# sonar_DAQ.net
KiCad netlist of a schematic drawn in Altium Designer
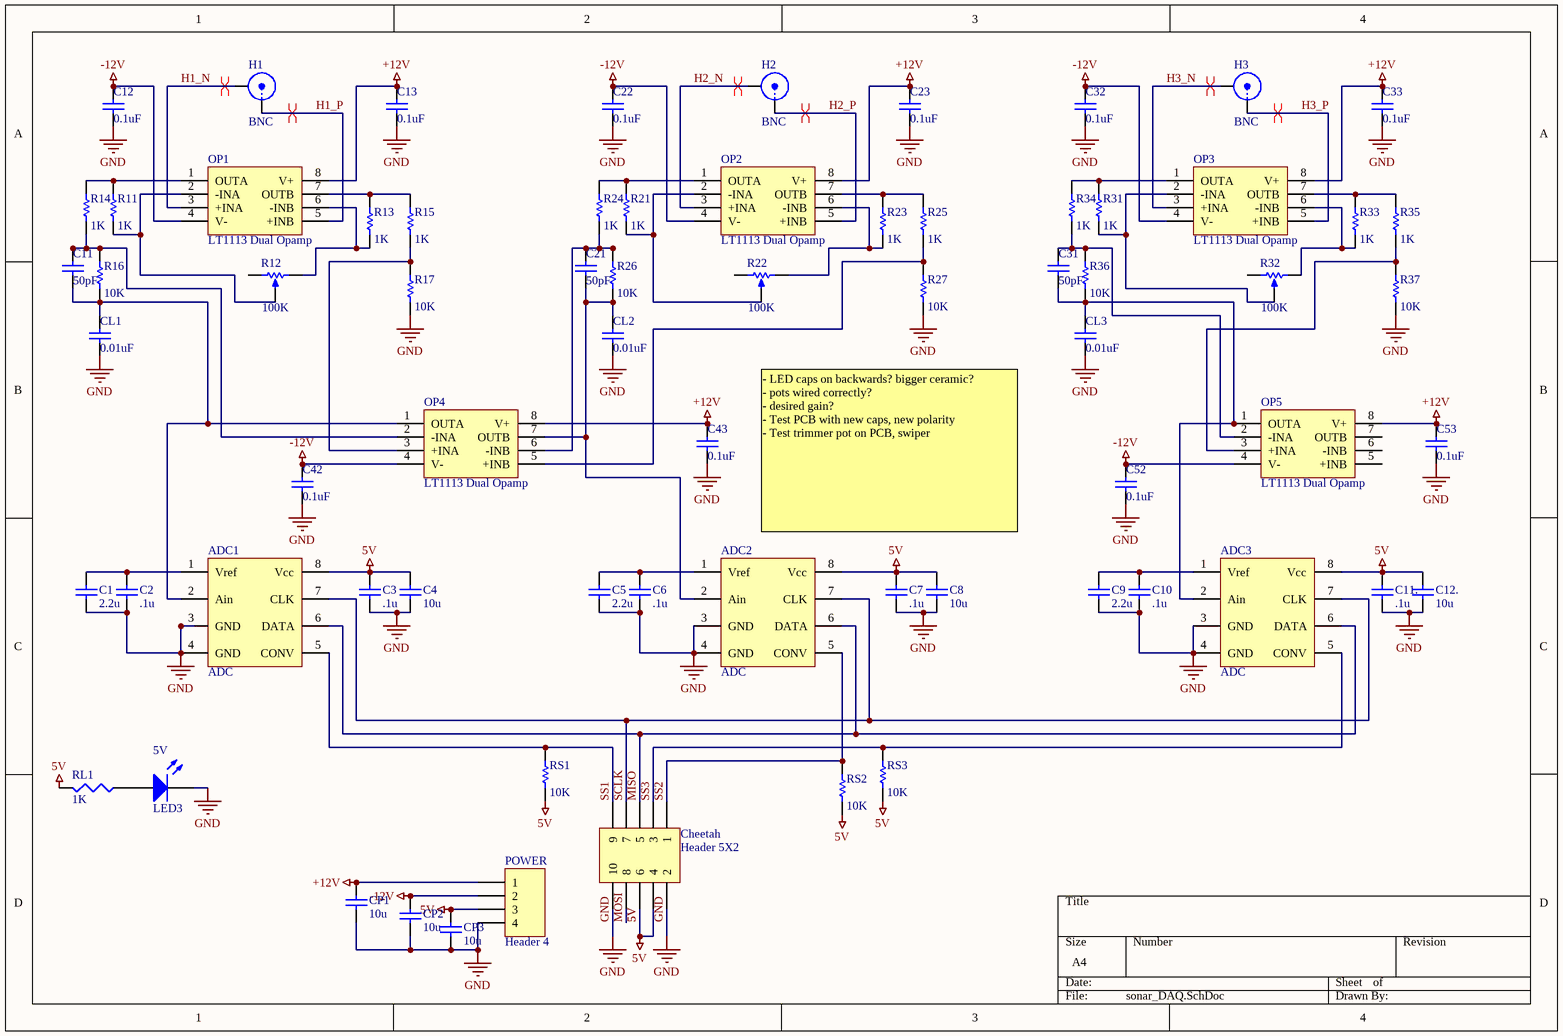
[diagram p0: sonar_DAQ.SchDoc]

(export (version "E")
  (design (tool "Eeschema 10.0.6"))
  (components
    (comp (ref "5V")
      (value "LED3")
      (footprint "0805_led")
      (description "Typical BLUE SiC LED")
      (fields (field (name "PUBLISHER") "Altium Limited"))
      (libsource (lib "Miscellaneous Devices") (part "LED3"))
    )
    (comp (ref "ADC1")
      (value "ADC")
      (footprint "ADC")
      (description "ADS7835")
      (libsource (lib "sonar_DAQ") (part "ADC"))
    )
    (comp (ref "ADC2")
      (value "ADC")
      (footprint "ADC")
      (description "ADS7835")
      (libsource (lib "sonar_DAQ") (part "ADC"))
    )
    (comp (ref "ADC3")
      (value "ADC")
      (footprint "ADC")
      (description "ADS7835")
      (libsource (lib "sonar_DAQ") (part "ADC"))
    )
    (comp (ref "C1")
      (value "2.2u")
      (footprint "0805_tantalum_cap")
      (description "Capacitor")
      (fields (field (name "PUBLISHER") "Altium Limited"))
      (libsource (lib "Miscellaneous Devices") (part "Cap"))
    )
    (comp (ref "C2")
      (value ".1u")
      (footprint "0805_ceramic_cap")
      (description "Capacitor")
      (fields (field (name "PUBLISHER") "Altium Limited"))
      (libsource (lib "Miscellaneous Devices") (part "Cap"))
    )
    (comp (ref "C3")
      (value ".1u")
      (footprint "0805_ceramic_cap")
      (description "Capacitor")
      (fields (field (name "PUBLISHER") "Altium Limited"))
      (libsource (lib "Miscellaneous Devices") (part "Cap"))
    )
    (comp (ref "C4")
      (value "10u")
      (footprint "0805_tantalum_cap")
      (description "Capacitor")
      (fields (field (name "PUBLISHER") "Altium Limited"))
      (libsource (lib "Miscellaneous Devices") (part "Cap"))
    )
    (comp (ref "C5")
      (value "2.2u")
      (footprint "0805_tantalum_cap")
      (description "Capacitor")
      (fields (field (name "PUBLISHER") "Altium Limited"))
      (libsource (lib "Miscellaneous Devices") (part "Cap"))
    )
    (comp (ref "C6")
      (value ".1u")
      (footprint "0805_ceramic_cap")
      (description "Capacitor")
      (fields (field (name "PUBLISHER") "Altium Limited"))
      (libsource (lib "Miscellaneous Devices") (part "Cap"))
    )
    (comp (ref "C7")
      (value ".1u")
      (footprint "0805_ceramic_cap")
      (description "Capacitor")
      (fields (field (name "PUBLISHER") "Altium Limited"))
      (libsource (lib "Miscellaneous Devices") (part "Cap"))
    )
    (comp (ref "C8")
      (value "10u")
      (footprint "0805_tantalum_cap")
      (description "Capacitor")
      (fields (field (name "PUBLISHER") "Altium Limited"))
      (libsource (lib "Miscellaneous Devices") (part "Cap"))
    )
    (comp (ref "C9")
      (value "2.2u")
      (footprint "0805_tantalum_cap")
      (description "Capacitor")
      (fields (field (name "PUBLISHER") "Altium Limited"))
      (libsource (lib "Miscellaneous Devices") (part "Cap"))
    )
    (comp (ref "C10")
      (value ".1u")
      (footprint "0805_ceramic_cap")
      (description "Capacitor")
      (fields (field (name "PUBLISHER") "Altium Limited"))
      (libsource (lib "Miscellaneous Devices") (part "Cap"))
    )
    (comp (ref "C11")
      (value "50pF")
      (footprint "0805_ceramic_cap")
      (description "Capacitor")
      (fields (field (name "Comment") "Cap") (field (name "PUBLISHER") "Altium Limited"))
      (libsource (lib "Miscellaneous Devices") (part "Cap"))
    )
    (comp (ref "C11.")
      (value ".1u")
      (footprint "0805_ceramic_cap")
      (description "Capacitor")
      (fields (field (name "PUBLISHER") "Altium Limited"))
      (libsource (lib "Miscellaneous Devices") (part "Cap"))
    )
    (comp (ref "C12")
      (value "0.1uF")
      (footprint "0805_ceramic_cap")
      (description "Capacitor")
      (fields (field (name "Comment") "Cap") (field (name "PUBLISHER") "Altium Limited"))
      (libsource (lib "Miscellaneous Devices") (part "Cap"))
    )
    (comp (ref "C12.")
      (value "10u")
      (footprint "0805_tantalum_cap")
      (description "Capacitor")
      (fields (field (name "PUBLISHER") "Altium Limited"))
      (libsource (lib "Miscellaneous Devices") (part "Cap"))
    )
    (comp (ref "C13")
      (value "0.1uF")
      (footprint "0805_ceramic_cap")
      (description "Capacitor")
      (fields (field (name "Comment") "Cap") (field (name "PUBLISHER") "Altium Limited"))
      (libsource (lib "Miscellaneous Devices") (part "Cap"))
    )
    (comp (ref "C21")
      (value "50pF")
      (footprint "0805_ceramic_cap")
      (description "Capacitor")
      (fields (field (name "Comment") "Cap") (field (name "PUBLISHER") "Altium Limited"))
      (libsource (lib "Miscellaneous Devices") (part "Cap"))
    )
    (comp (ref "C22")
      (value "0.1uF")
      (footprint "0805_ceramic_cap")
      (description "Capacitor")
      (fields (field (name "Comment") "Cap") (field (name "PUBLISHER") "Altium Limited"))
      (libsource (lib "Miscellaneous Devices") (part "Cap"))
    )
    (comp (ref "C23")
      (value "0.1uF")
      (footprint "0805_ceramic_cap")
      (description "Capacitor")
      (fields (field (name "Comment") "Cap") (field (name "PUBLISHER") "Altium Limited"))
      (libsource (lib "Miscellaneous Devices") (part "Cap"))
    )
    (comp (ref "C31")
      (value "50pF")
      (footprint "0805_ceramic_cap")
      (description "Capacitor")
      (fields (field (name "Comment") "Cap") (field (name "PUBLISHER") "Altium Limited"))
      (libsource (lib "Miscellaneous Devices") (part "Cap"))
    )
    (comp (ref "C32")
      (value "0.1uF")
      (footprint "0805_ceramic_cap")
      (description "Capacitor")
      (fields (field (name "Comment") "Cap") (field (name "PUBLISHER") "Altium Limited"))
      (libsource (lib "Miscellaneous Devices") (part "Cap"))
    )
    (comp (ref "C33")
      (value "0.1uF")
      (footprint "0805_ceramic_cap")
      (description "Capacitor")
      (fields (field (name "Comment") "Cap") (field (name "PUBLISHER") "Altium Limited"))
      (libsource (lib "Miscellaneous Devices") (part "Cap"))
    )
    (comp (ref "C42")
      (value "0.1uF")
      (footprint "0805_ceramic_cap")
      (description "Capacitor")
      (fields (field (name "Comment") "Cap") (field (name "PUBLISHER") "Altium Limited"))
      (libsource (lib "Miscellaneous Devices") (part "Cap"))
    )
    (comp (ref "C43")
      (value "0.1uF")
      (footprint "0805_ceramic_cap")
      (description "Capacitor")
      (fields (field (name "Comment") "Cap") (field (name "PUBLISHER") "Altium Limited"))
      (libsource (lib "Miscellaneous Devices") (part "Cap"))
    )
    (comp (ref "C52")
      (value "0.1uF")
      (footprint "0805_ceramic_cap")
      (description "Capacitor")
      (fields (field (name "Comment") "Cap") (field (name "PUBLISHER") "Altium Limited"))
      (libsource (lib "Miscellaneous Devices") (part "Cap"))
    )
    (comp (ref "C53")
      (value "0.1uF")
      (footprint "0805_ceramic_cap")
      (description "Capacitor")
      (fields (field (name "Comment") "Cap") (field (name "PUBLISHER") "Altium Limited"))
      (libsource (lib "Miscellaneous Devices") (part "Cap"))
    )
    (comp (ref "Cheetah")
      (value "Header 5X2")
      (footprint "HDR2X5")
      (description "Header, 5-Pin, Dual row")
      (fields (field (name "PUBLISHER") "Altium Limited"))
      (libsource (lib "Miscellaneous Connectors") (part "Header 5X2"))
    )
    (comp (ref "CL1")
      (value "0.01uF")
      (footprint "0805_ceramic_cap")
      (description "Capacitor")
      (fields (field (name "Comment") "Cap") (field (name "PUBLISHER") "Altium Limited"))
      (libsource (lib "Miscellaneous Devices") (part "Cap"))
    )
    (comp (ref "CL2")
      (value "0.01uF")
      (footprint "0805_ceramic_cap")
      (description "Capacitor")
      (fields (field (name "Comment") "Cap") (field (name "PUBLISHER") "Altium Limited"))
      (libsource (lib "Miscellaneous Devices") (part "Cap"))
    )
    (comp (ref "CL3")
      (value "0.01uF")
      (footprint "0805_ceramic_cap")
      (description "Capacitor")
      (fields (field (name "Comment") "Cap") (field (name "PUBLISHER") "Altium Limited"))
      (libsource (lib "Miscellaneous Devices") (part "Cap"))
    )
    (comp (ref "CP1")
      (value "10u")
      (footprint "1210_cap")
      (description "Capacitor")
      (fields (field (name "PUBLISHER") "Altium Limited"))
      (libsource (lib "Miscellaneous Devices") (part "Cap"))
    )
    (comp (ref "CP2")
      (value "10u")
      (footprint "1210_cap")
      (description "Capacitor")
      (fields (field (name "PUBLISHER") "Altium Limited"))
      (libsource (lib "Miscellaneous Devices") (part "Cap"))
    )
    (comp (ref "CP3")
      (value "10u")
      (footprint "1210_cap")
      (description "Capacitor")
      (fields (field (name "PUBLISHER") "Altium Limited"))
      (libsource (lib "Miscellaneous Devices") (part "Cap"))
    )
    (comp (ref "H1")
      (value "BNC")
      (footprint "BNC")
      (description "BNC Elbow Connector")
      (fields (field (name "PUBLISHER") "Altium Limited"))
      (libsource (lib "Miscellaneous Connectors") (part "BNC"))
    )
    (comp (ref "H2")
      (value "BNC")
      (footprint "BNC")
      (description "BNC Elbow Connector")
      (fields (field (name "PUBLISHER") "Altium Limited"))
      (libsource (lib "Miscellaneous Connectors") (part "BNC"))
    )
    (comp (ref "H3")
      (value "BNC")
      (footprint "BNC")
      (description "BNC Elbow Connector")
      (fields (field (name "PUBLISHER") "Altium Limited"))
      (libsource (lib "Miscellaneous Connectors") (part "BNC"))
    )
    (comp (ref "OP1")
      (value "LT1113 Dual Opamp")
      (footprint "lt1113_opamp")
      (libsource (lib "sonar_DAQ") (part "LT1113 OPAMP"))
    )
    (comp (ref "OP2")
      (value "LT1113 Dual Opamp")
      (footprint "lt1113_opamp")
      (libsource (lib "sonar_DAQ") (part "LT1113 OPAMP"))
    )
    (comp (ref "OP3")
      (value "LT1113 Dual Opamp")
      (footprint "lt1113_opamp")
      (libsource (lib "sonar_DAQ") (part "LT1113 OPAMP"))
    )
    (comp (ref "OP4")
      (value "LT1113 Dual Opamp")
      (footprint "lt1113_opamp")
      (libsource (lib "sonar_DAQ") (part "LT1113 OPAMP"))
    )
    (comp (ref "OP5")
      (value "LT1113 Dual Opamp")
      (footprint "lt1113_opamp")
      (libsource (lib "sonar_DAQ") (part "LT1113 OPAMP"))
    )
    (comp (ref "POWER")
      (value "Header 4")
      (footprint "HDR1X4")
      (description "Header, 4-Pin")
      (fields (field (name "PUBLISHER") "Altium Limited"))
      (libsource (lib "Miscellaneous Connectors") (part "Header 4"))
    )
    (comp (ref "R11")
      (value "1K")
      (footprint "0805_res")
      (description "Resistor")
      (fields (field (name "Comment") "Res1") (field (name "PUBLISHER") "Altium Limited"))
      (libsource (lib "Miscellaneous Devices") (part "Res1"))
    )
    (comp (ref "R12")
      (value "100K")
      (footprint "trimmer_pot")
      (description "Potentiometer")
      (fields (field (name "Comment") "RPot") (field (name "PUBLISHER") "Altium Limited"))
      (libsource (lib "Miscellaneous Devices") (part "RPot"))
    )
    (comp (ref "R13")
      (value "1K")
      (footprint "0805_res")
      (description "Resistor")
      (fields (field (name "Comment") "Res1") (field (name "PUBLISHER") "Altium Limited"))
      (libsource (lib "Miscellaneous Devices") (part "Res1"))
    )
    (comp (ref "R14")
      (value "1K")
      (footprint "0805_res")
      (description "Resistor")
      (fields (field (name "Comment") "Res1") (field (name "PUBLISHER") "Altium Limited"))
      (libsource (lib "Miscellaneous Devices") (part "Res1"))
    )
    (comp (ref "R15")
      (value "1K")
      (footprint "0805_res")
      (description "Resistor")
      (fields (field (name "Comment") "Res1") (field (name "PUBLISHER") "Altium Limited"))
      (libsource (lib "Miscellaneous Devices") (part "Res1"))
    )
    (comp (ref "R16")
      (value "10K")
      (footprint "0805_res")
      (description "Resistor")
      (fields (field (name "Comment") "Res1") (field (name "PUBLISHER") "Altium Limited"))
      (libsource (lib "Miscellaneous Devices") (part "Res1"))
    )
    (comp (ref "R17")
      (value "10K")
      (footprint "0805_res")
      (description "Resistor")
      (fields (field (name "Comment") "Res1") (field (name "PUBLISHER") "Altium Limited"))
      (libsource (lib "Miscellaneous Devices") (part "Res1"))
    )
    (comp (ref "R21")
      (value "1K")
      (footprint "0805_res")
      (description "Resistor")
      (fields (field (name "Comment") "Res1") (field (name "PUBLISHER") "Altium Limited"))
      (libsource (lib "Miscellaneous Devices") (part "Res1"))
    )
    (comp (ref "R22")
      (value "100K")
      (footprint "trimmer_pot")
      (description "Potentiometer")
      (fields (field (name "Comment") "RPot") (field (name "PUBLISHER") "Altium Limited"))
      (libsource (lib "Miscellaneous Devices") (part "RPot"))
    )
    (comp (ref "R23")
      (value "1K")
      (footprint "0805_res")
      (description "Resistor")
      (fields (field (name "Comment") "Res1") (field (name "PUBLISHER") "Altium Limited"))
      (libsource (lib "Miscellaneous Devices") (part "Res1"))
    )
    (comp (ref "R24")
      (value "1K")
      (footprint "0805_res")
      (description "Resistor")
      (fields (field (name "Comment") "Res1") (field (name "PUBLISHER") "Altium Limited"))
      (libsource (lib "Miscellaneous Devices") (part "Res1"))
    )
    (comp (ref "R25")
      (value "1K")
      (footprint "0805_res")
      (description "Resistor")
      (fields (field (name "Comment") "Res1") (field (name "PUBLISHER") "Altium Limited"))
      (libsource (lib "Miscellaneous Devices") (part "Res1"))
    )
    (comp (ref "R26")
      (value "10K")
      (footprint "0805_res")
      (description "Resistor")
      (fields (field (name "Comment") "Res1") (field (name "PUBLISHER") "Altium Limited"))
      (libsource (lib "Miscellaneous Devices") (part "Res1"))
    )
    (comp (ref "R27")
      (value "10K")
      (footprint "0805_res")
      (description "Resistor")
      (fields (field (name "Comment") "Res1") (field (name "PUBLISHER") "Altium Limited"))
      (libsource (lib "Miscellaneous Devices") (part "Res1"))
    )
    (comp (ref "R31")
      (value "1K")
      (footprint "0805_res")
      (description "Resistor")
      (fields (field (name "Comment") "Res1") (field (name "PUBLISHER") "Altium Limited"))
      (libsource (lib "Miscellaneous Devices") (part "Res1"))
    )
    (comp (ref "R32")
      (value "100K")
      (footprint "trimmer_pot")
      (description "Potentiometer")
      (fields (field (name "Comment") "RPot") (field (name "PUBLISHER") "Altium Limited"))
      (libsource (lib "Miscellaneous Devices") (part "RPot"))
    )
    (comp (ref "R33")
      (value "1K")
      (footprint "0805_res")
      (description "Resistor")
      (fields (field (name "Comment") "Res1") (field (name "PUBLISHER") "Altium Limited"))
      (libsource (lib "Miscellaneous Devices") (part "Res1"))
    )
    (comp (ref "R34")
      (value "1K")
      (footprint "0805_res")
      (description "Resistor")
      (fields (field (name "Comment") "Res1") (field (name "PUBLISHER") "Altium Limited"))
      (libsource (lib "Miscellaneous Devices") (part "Res1"))
    )
    (comp (ref "R35")
      (value "1K")
      (footprint "0805_res")
      (description "Resistor")
      (fields (field (name "Comment") "Res1") (field (name "PUBLISHER") "Altium Limited"))
      (libsource (lib "Miscellaneous Devices") (part "Res1"))
    )
    (comp (ref "R36")
      (value "10K")
      (footprint "0805_res")
      (description "Resistor")
      (fields (field (name "Comment") "Res1") (field (name "PUBLISHER") "Altium Limited"))
      (libsource (lib "Miscellaneous Devices") (part "Res1"))
    )
    (comp (ref "R37")
      (value "10K")
      (footprint "0805_res")
      (description "Resistor")
      (fields (field (name "Comment") "Res1") (field (name "PUBLISHER") "Altium Limited"))
      (libsource (lib "Miscellaneous Devices") (part "Res1"))
    )
    (comp (ref "RL1")
      (value "1K")
      (footprint "0805_res")
      (description "Resistor")
      (fields (field (name "Comment") "Res3") (field (name "PUBLISHER") "Altium Limited"))
      (libsource (lib "Miscellaneous Devices") (part "Res3"))
    )
    (comp (ref "RS1")
      (value "10K")
      (footprint "0805_res")
      (description "Resistor")
      (fields (field (name "Comment") "Res1") (field (name "PUBLISHER") "Altium Limited"))
      (libsource (lib "Miscellaneous Devices") (part "Res1"))
    )
    (comp (ref "RS2")
      (value "10K")
      (footprint "0805_res")
      (description "Resistor")
      (fields (field (name "Comment") "Res1") (field (name "PUBLISHER") "Altium Limited"))
      (libsource (lib "Miscellaneous Devices") (part "Res1"))
    )
    (comp (ref "RS3")
      (value "10K")
      (footprint "0805_res")
      (description "Resistor")
      (fields (field (name "Comment") "Res1") (field (name "PUBLISHER") "Altium Limited"))
      (libsource (lib "Miscellaneous Devices") (part "Res1"))
    )
  )
  (nets
    (net (code "1") (name "+12V") (class "Default")
      (node (ref "C13") (pin "2") (pinfunction "2_2") (pintype "passive"))
      (node (ref "C23") (pin "2") (pinfunction "2_2") (pintype "passive"))
      (node (ref "C33") (pin "2") (pinfunction "2_2") (pintype "passive"))
      (node (ref "C43") (pin "2") (pinfunction "2_2") (pintype "passive"))
      (node (ref "C53") (pin "2") (pinfunction "2_2") (pintype "passive"))
      (node (ref "CP1") (pin "1") (pinfunction "1_1") (pintype "passive"))
      (node (ref "OP1") (pin "8") (pinfunction "V+_8") (pintype "power_in"))
      (node (ref "OP2") (pin "8") (pinfunction "V+_8") (pintype "power_in"))
      (node (ref "OP3") (pin "8") (pinfunction "V+_8") (pintype "power_in"))
      (node (ref "OP4") (pin "8") (pinfunction "V+_8") (pintype "power_in"))
      (node (ref "OP5") (pin "8") (pinfunction "V+_8") (pintype "power_in"))
      (node (ref "POWER") (pin "1") (pinfunction "1_1") (pintype "passive"))
    )
    (net (code "2") (name "-12V") (class "Default")
      (node (ref "C12") (pin "2") (pinfunction "2_2") (pintype "passive"))
      (node (ref "C22") (pin "2") (pinfunction "2_2") (pintype "passive"))
      (node (ref "C32") (pin "2") (pinfunction "2_2") (pintype "passive"))
      (node (ref "C42") (pin "2") (pinfunction "2_2") (pintype "passive"))
      (node (ref "C52") (pin "2") (pinfunction "2_2") (pintype "passive"))
      (node (ref "CP2") (pin "1") (pinfunction "1_1") (pintype "passive"))
      (node (ref "OP1") (pin "4") (pinfunction "V-_4") (pintype "power_in"))
      (node (ref "OP2") (pin "4") (pinfunction "V-_4") (pintype "power_in"))
      (node (ref "OP3") (pin "4") (pinfunction "V-_4") (pintype "power_in"))
      (node (ref "OP4") (pin "4") (pinfunction "V-_4") (pintype "power_in"))
      (node (ref "OP5") (pin "4") (pinfunction "V-_4") (pintype "power_in"))
      (node (ref "POWER") (pin "2") (pinfunction "2_2") (pintype "passive"))
    )
    (net (code "3") (name "/H1_N") (class "Default")
      (node (ref "H1") (pin "2") (pinfunction "Y_2") (pintype "passive"))
      (node (ref "OP1") (pin "3") (pinfunction "+INA_3") (pintype "power_in"))
    )
    (net (code "4") (name "/H1_P") (class "Default")
      (node (ref "H1") (pin "1") (pinfunction "X_1") (pintype "passive"))
      (node (ref "OP1") (pin "5") (pinfunction "+INB_5") (pintype "power_in"))
    )
    (net (code "5") (name "/H2_N") (class "Default")
      (node (ref "H2") (pin "2") (pinfunction "Y_2") (pintype "passive"))
      (node (ref "OP2") (pin "3") (pinfunction "+INA_3") (pintype "power_in"))
    )
    (net (code "6") (name "/H2_P") (class "Default")
      (node (ref "H2") (pin "1") (pinfunction "X_1") (pintype "passive"))
      (node (ref "OP2") (pin "5") (pinfunction "+INB_5") (pintype "power_in"))
    )
    (net (code "7") (name "/H3_N") (class "Default")
      (node (ref "H3") (pin "2") (pinfunction "Y_2") (pintype "passive"))
      (node (ref "OP3") (pin "3") (pinfunction "+INA_3") (pintype "power_in"))
    )
    (net (code "8") (name "/H3_P") (class "Default")
      (node (ref "H3") (pin "1") (pinfunction "X_1") (pintype "passive"))
      (node (ref "OP3") (pin "5") (pinfunction "+INB_5") (pintype "power_in"))
    )
    (net (code "9") (name "/MISO") (class "Default")
      (node (ref "ADC1") (pin "6") (pinfunction "DATA_6") (pintype "power_in"))
      (node (ref "ADC2") (pin "6") (pinfunction "DATA_6") (pintype "power_in"))
      (node (ref "ADC3") (pin "6") (pinfunction "DATA_6") (pintype "power_in"))
      (node (ref "Cheetah") (pin "5") (pinfunction "5_5") (pintype "passive"))
    )
    (net (code "10") (name "/MOSI") (class "Default")
      (node (ref "Cheetah") (pin "8") (pinfunction "8_8") (pintype "passive"))
    )
    (net (code "11") (name "/SCLK") (class "Default")
      (node (ref "ADC1") (pin "7") (pinfunction "CLK_7") (pintype "power_in"))
      (node (ref "ADC2") (pin "7") (pinfunction "CLK_7") (pintype "power_in"))
      (node (ref "ADC3") (pin "7") (pinfunction "CLK_7") (pintype "power_in"))
      (node (ref "Cheetah") (pin "7") (pinfunction "7_7") (pintype "passive"))
    )
    (net (code "12") (name "/SS1") (class "Default")
      (node (ref "ADC1") (pin "5") (pinfunction "CONV_5") (pintype "power_in"))
      (node (ref "Cheetah") (pin "9") (pinfunction "9_9") (pintype "passive"))
      (node (ref "RS1") (pin "2") (pinfunction "2_2") (pintype "passive"))
    )
    (net (code "13") (name "/SS2") (class "Default")
      (node (ref "ADC2") (pin "5") (pinfunction "CONV_5") (pintype "power_in"))
      (node (ref "Cheetah") (pin "1") (pinfunction "1_1") (pintype "passive"))
      (node (ref "RS2") (pin "2") (pinfunction "2_2") (pintype "passive"))
    )
    (net (code "14") (name "/SS3") (class "Default")
      (node (ref "ADC3") (pin "5") (pinfunction "CONV_5") (pintype "power_in"))
      (node (ref "Cheetah") (pin "3") (pinfunction "3_3") (pintype "passive"))
      (node (ref "RS3") (pin "2") (pinfunction "2_2") (pintype "passive"))
    )
    (net (code "15") (name "5V") (class "Default")
      (node (ref "ADC1") (pin "8") (pinfunction "Vcc_8") (pintype "power_in"))
      (node (ref "ADC2") (pin "8") (pinfunction "Vcc_8") (pintype "power_in"))
      (node (ref "ADC3") (pin "8") (pinfunction "Vcc_8") (pintype "power_in"))
      (node (ref "C11.") (pin "1") (pinfunction "1_1") (pintype "passive"))
      (node (ref "C12.") (pin "1") (pinfunction "1_1") (pintype "passive"))
      (node (ref "C3") (pin "1") (pinfunction "1_1") (pintype "passive"))
      (node (ref "C4") (pin "1") (pinfunction "1_1") (pintype "passive"))
      (node (ref "C7") (pin "1") (pinfunction "1_1") (pintype "passive"))
      (node (ref "C8") (pin "1") (pinfunction "1_1") (pintype "passive"))
      (node (ref "CP3") (pin "1") (pinfunction "1_1") (pintype "passive"))
      (node (ref "Cheetah") (pin "4") (pinfunction "4_4") (pintype "passive"))
      (node (ref "Cheetah") (pin "6") (pinfunction "6_6") (pintype "passive"))
      (node (ref "POWER") (pin "3") (pinfunction "3_3") (pintype "passive"))
      (node (ref "RL1") (pin "2") (pinfunction "2_2") (pintype "passive"))
      (node (ref "RS1") (pin "1") (pinfunction "1_1") (pintype "passive"))
      (node (ref "RS2") (pin "1") (pinfunction "1_1") (pintype "passive"))
      (node (ref "RS3") (pin "1") (pinfunction "1_1") (pintype "passive"))
    )
    (net (code "16") (name "GND") (class "Default")
      (node (ref "5V") (pin "2") (pinfunction "K_2") (pintype "passive"))
      (node (ref "ADC1") (pin "3") (pinfunction "GND_3") (pintype "power_in"))
      (node (ref "ADC1") (pin "4") (pinfunction "GND_4") (pintype "power_in"))
      (node (ref "ADC2") (pin "3") (pinfunction "GND_3") (pintype "power_in"))
      (node (ref "ADC2") (pin "4") (pinfunction "GND_4") (pintype "power_in"))
      (node (ref "ADC3") (pin "3") (pinfunction "GND_3") (pintype "power_in"))
      (node (ref "ADC3") (pin "4") (pinfunction "GND_4") (pintype "power_in"))
      (node (ref "C1") (pin "2") (pinfunction "2_2") (pintype "passive"))
      (node (ref "C10") (pin "2") (pinfunction "2_2") (pintype "passive"))
      (node (ref "C11.") (pin "2") (pinfunction "2_2") (pintype "passive"))
      (node (ref "C12") (pin "1") (pinfunction "1_1") (pintype "passive"))
      (node (ref "C12.") (pin "2") (pinfunction "2_2") (pintype "passive"))
      (node (ref "C13") (pin "1") (pinfunction "1_1") (pintype "passive"))
      (node (ref "C2") (pin "2") (pinfunction "2_2") (pintype "passive"))
      (node (ref "C22") (pin "1") (pinfunction "1_1") (pintype "passive"))
      (node (ref "C23") (pin "1") (pinfunction "1_1") (pintype "passive"))
      (node (ref "C3") (pin "2") (pinfunction "2_2") (pintype "passive"))
      (node (ref "C32") (pin "1") (pinfunction "1_1") (pintype "passive"))
      (node (ref "C33") (pin "1") (pinfunction "1_1") (pintype "passive"))
      (node (ref "C4") (pin "2") (pinfunction "2_2") (pintype "passive"))
      (node (ref "C42") (pin "1") (pinfunction "1_1") (pintype "passive"))
      (node (ref "C43") (pin "1") (pinfunction "1_1") (pintype "passive"))
      (node (ref "C5") (pin "2") (pinfunction "2_2") (pintype "passive"))
      (node (ref "C52") (pin "1") (pinfunction "1_1") (pintype "passive"))
      (node (ref "C53") (pin "1") (pinfunction "1_1") (pintype "passive"))
      (node (ref "C6") (pin "2") (pinfunction "2_2") (pintype "passive"))
      (node (ref "C7") (pin "2") (pinfunction "2_2") (pintype "passive"))
      (node (ref "C8") (pin "2") (pinfunction "2_2") (pintype "passive"))
      (node (ref "C9") (pin "2") (pinfunction "2_2") (pintype "passive"))
      (node (ref "CL1") (pin "2") (pinfunction "2_2") (pintype "passive"))
      (node (ref "CL2") (pin "2") (pinfunction "2_2") (pintype "passive"))
      (node (ref "CL3") (pin "2") (pinfunction "2_2") (pintype "passive"))
      (node (ref "CP1") (pin "2") (pinfunction "2_2") (pintype "passive"))
      (node (ref "CP2") (pin "2") (pinfunction "2_2") (pintype "passive"))
      (node (ref "CP3") (pin "2") (pinfunction "2_2") (pintype "passive"))
      (node (ref "Cheetah") (pin "10") (pinfunction "10_10") (pintype "passive"))
      (node (ref "Cheetah") (pin "2") (pinfunction "2_2") (pintype "passive"))
      (node (ref "POWER") (pin "4") (pinfunction "4_4") (pintype "passive"))
      (node (ref "R17") (pin "1") (pinfunction "1_1") (pintype "passive"))
      (node (ref "R27") (pin "1") (pinfunction "1_1") (pintype "passive"))
      (node (ref "R37") (pin "1") (pinfunction "1_1") (pintype "passive"))
    )
    (net (code "17") (name "Net-(5V-A)") (class "Default")
      (node (ref "5V") (pin "1") (pinfunction "A_1") (pintype "passive"))
      (node (ref "RL1") (pin "1") (pinfunction "1_1") (pintype "passive"))
    )
    (net (code "18") (name "Net-(ADC1-Ain)") (class "Default")
      (node (ref "ADC1") (pin "2") (pinfunction "Ain_2") (pintype "power_in"))
      (node (ref "C11") (pin "1") (pinfunction "1_1") (pintype "passive"))
      (node (ref "CL1") (pin "1") (pinfunction "1_1") (pintype "passive"))
      (node (ref "OP4") (pin "1") (pinfunction "OUTA_1") (pintype "power_in"))
      (node (ref "R16") (pin "1") (pinfunction "1_1") (pintype "passive"))
    )
    (net (code "19") (name "Net-(ADC1-Vref)") (class "Default")
      (node (ref "ADC1") (pin "1") (pinfunction "Vref_1") (pintype "power_in"))
      (node (ref "C1") (pin "1") (pinfunction "1_1") (pintype "passive"))
      (node (ref "C2") (pin "1") (pinfunction "1_1") (pintype "passive"))
    )
    (net (code "20") (name "Net-(ADC2-Ain)") (class "Default")
      (node (ref "ADC2") (pin "2") (pinfunction "Ain_2") (pintype "power_in"))
      (node (ref "C21") (pin "1") (pinfunction "1_1") (pintype "passive"))
      (node (ref "CL2") (pin "1") (pinfunction "1_1") (pintype "passive"))
      (node (ref "OP4") (pin "7") (pinfunction "OUTB_7") (pintype "power_in"))
      (node (ref "R26") (pin "1") (pinfunction "1_1") (pintype "passive"))
    )
    (net (code "21") (name "Net-(ADC2-Vref)") (class "Default")
      (node (ref "ADC2") (pin "1") (pinfunction "Vref_1") (pintype "power_in"))
      (node (ref "C5") (pin "1") (pinfunction "1_1") (pintype "passive"))
      (node (ref "C6") (pin "1") (pinfunction "1_1") (pintype "passive"))
    )
    (net (code "22") (name "Net-(ADC3-Ain)") (class "Default")
      (node (ref "ADC3") (pin "2") (pinfunction "Ain_2") (pintype "power_in"))
      (node (ref "C31") (pin "1") (pinfunction "1_1") (pintype "passive"))
      (node (ref "CL3") (pin "1") (pinfunction "1_1") (pintype "passive"))
      (node (ref "OP5") (pin "1") (pinfunction "OUTA_1") (pintype "power_in"))
      (node (ref "R36") (pin "1") (pinfunction "1_1") (pintype "passive"))
    )
    (net (code "23") (name "Net-(ADC3-Vref)") (class "Default")
      (node (ref "ADC3") (pin "1") (pinfunction "Vref_1") (pintype "power_in"))
      (node (ref "C10") (pin "1") (pinfunction "1_1") (pintype "passive"))
      (node (ref "C9") (pin "1") (pinfunction "1_1") (pintype "passive"))
    )
    (net (code "24") (name "Net-(OP1--INA)") (class "Default")
      (node (ref "OP1") (pin "2") (pinfunction "-INA_2") (pintype "power_in"))
      (node (ref "R11") (pin "1") (pinfunction "1_1") (pintype "passive"))
      (node (ref "R12") (pin "3") (pinfunction "TAP_3") (pintype "passive"))
    )
    (net (code "25") (name "Net-(OP1--INB)") (class "Default")
      (node (ref "OP1") (pin "6") (pinfunction "-INB_6") (pintype "power_in"))
      (node (ref "R12") (pin "2") (pinfunction "BOT_2") (pintype "passive"))
      (node (ref "R13") (pin "1") (pinfunction "1_1") (pintype "passive"))
    )
    (net (code "26") (name "Net-(OP1-OUTA)") (class "Default")
      (node (ref "OP1") (pin "1") (pinfunction "OUTA_1") (pintype "power_in"))
      (node (ref "R11") (pin "2") (pinfunction "2_2") (pintype "passive"))
      (node (ref "R14") (pin "2") (pinfunction "2_2") (pintype "passive"))
    )
    (net (code "27") (name "Net-(OP1-OUTB)") (class "Default")
      (node (ref "OP1") (pin "7") (pinfunction "OUTB_7") (pintype "power_in"))
      (node (ref "R13") (pin "2") (pinfunction "2_2") (pintype "passive"))
      (node (ref "R15") (pin "2") (pinfunction "2_2") (pintype "passive"))
    )
    (net (code "28") (name "Net-(OP2--INA)") (class "Default")
      (node (ref "OP2") (pin "2") (pinfunction "-INA_2") (pintype "power_in"))
      (node (ref "R21") (pin "1") (pinfunction "1_1") (pintype "passive"))
      (node (ref "R22") (pin "3") (pinfunction "TAP_3") (pintype "passive"))
    )
    (net (code "29") (name "Net-(OP2--INB)") (class "Default")
      (node (ref "OP2") (pin "6") (pinfunction "-INB_6") (pintype "power_in"))
      (node (ref "R22") (pin "2") (pinfunction "BOT_2") (pintype "passive"))
      (node (ref "R23") (pin "1") (pinfunction "1_1") (pintype "passive"))
    )
    (net (code "30") (name "Net-(OP2-OUTA)") (class "Default")
      (node (ref "OP2") (pin "1") (pinfunction "OUTA_1") (pintype "power_in"))
      (node (ref "R21") (pin "2") (pinfunction "2_2") (pintype "passive"))
      (node (ref "R24") (pin "2") (pinfunction "2_2") (pintype "passive"))
    )
    (net (code "31") (name "Net-(OP2-OUTB)") (class "Default")
      (node (ref "OP2") (pin "7") (pinfunction "OUTB_7") (pintype "power_in"))
      (node (ref "R23") (pin "2") (pinfunction "2_2") (pintype "passive"))
      (node (ref "R25") (pin "2") (pinfunction "2_2") (pintype "passive"))
    )
    (net (code "32") (name "Net-(OP3--INA)") (class "Default")
      (node (ref "OP3") (pin "2") (pinfunction "-INA_2") (pintype "power_in"))
      (node (ref "R31") (pin "1") (pinfunction "1_1") (pintype "passive"))
      (node (ref "R32") (pin "3") (pinfunction "TAP_3") (pintype "passive"))
    )
    (net (code "33") (name "Net-(OP3--INB)") (class "Default")
      (node (ref "OP3") (pin "6") (pinfunction "-INB_6") (pintype "power_in"))
      (node (ref "R32") (pin "2") (pinfunction "BOT_2") (pintype "passive"))
      (node (ref "R33") (pin "1") (pinfunction "1_1") (pintype "passive"))
    )
    (net (code "34") (name "Net-(OP3-OUTA)") (class "Default")
      (node (ref "OP3") (pin "1") (pinfunction "OUTA_1") (pintype "power_in"))
      (node (ref "R31") (pin "2") (pinfunction "2_2") (pintype "passive"))
      (node (ref "R34") (pin "2") (pinfunction "2_2") (pintype "passive"))
    )
    (net (code "35") (name "Net-(OP3-OUTB)") (class "Default")
      (node (ref "OP3") (pin "7") (pinfunction "OUTB_7") (pintype "power_in"))
      (node (ref "R33") (pin "2") (pinfunction "2_2") (pintype "passive"))
      (node (ref "R35") (pin "2") (pinfunction "2_2") (pintype "passive"))
    )
    (net (code "36") (name "Net-(OP4-+INA)") (class "Default")
      (node (ref "OP4") (pin "3") (pinfunction "+INA_3") (pintype "power_in"))
      (node (ref "R15") (pin "1") (pinfunction "1_1") (pintype "passive"))
      (node (ref "R17") (pin "2") (pinfunction "2_2") (pintype "passive"))
    )
    (net (code "37") (name "Net-(OP4-+INB)") (class "Default")
      (node (ref "OP4") (pin "5") (pinfunction "+INB_5") (pintype "power_in"))
      (node (ref "R25") (pin "1") (pinfunction "1_1") (pintype "passive"))
      (node (ref "R27") (pin "2") (pinfunction "2_2") (pintype "passive"))
    )
    (net (code "38") (name "Net-(OP4--INA)") (class "Default")
      (node (ref "C11") (pin "2") (pinfunction "2_2") (pintype "passive"))
      (node (ref "OP4") (pin "2") (pinfunction "-INA_2") (pintype "power_in"))
      (node (ref "R14") (pin "1") (pinfunction "1_1") (pintype "passive"))
      (node (ref "R16") (pin "2") (pinfunction "2_2") (pintype "passive"))
    )
    (net (code "39") (name "Net-(OP4--INB)") (class "Default")
      (node (ref "C21") (pin "2") (pinfunction "2_2") (pintype "passive"))
      (node (ref "OP4") (pin "6") (pinfunction "-INB_6") (pintype "power_in"))
      (node (ref "R24") (pin "1") (pinfunction "1_1") (pintype "passive"))
      (node (ref "R26") (pin "2") (pinfunction "2_2") (pintype "passive"))
    )
    (net (code "40") (name "Net-(OP5-+INA)") (class "Default")
      (node (ref "OP5") (pin "3") (pinfunction "+INA_3") (pintype "power_in"))
      (node (ref "R35") (pin "1") (pinfunction "1_1") (pintype "passive"))
      (node (ref "R37") (pin "2") (pinfunction "2_2") (pintype "passive"))
    )
    (net (code "41") (name "Net-(OP5--INA)") (class "Default")
      (node (ref "C31") (pin "2") (pinfunction "2_2") (pintype "passive"))
      (node (ref "OP5") (pin "2") (pinfunction "-INA_2") (pintype "power_in"))
      (node (ref "R34") (pin "1") (pinfunction "1_1") (pintype "passive"))
      (node (ref "R36") (pin "2") (pinfunction "2_2") (pintype "passive"))
    )
    (net (code "42") (name "unconnected-(OP5-+INB-Pad5)") (class "Default")
      (node (ref "OP5") (pin "5") (pinfunction "+INB_5") (pintype "power_in"))
    )
    (net (code "43") (name "unconnected-(OP5--INB-Pad6)") (class "Default")
      (node (ref "OP5") (pin "6") (pinfunction "-INB_6") (pintype "power_in"))
    )
    (net (code "44") (name "unconnected-(OP5-OUTB-Pad7)") (class "Default")
      (node (ref "OP5") (pin "7") (pinfunction "OUTB_7") (pintype "power_in"))
    )
    (net (code "45") (name "unconnected-(R12-TOP-Pad1)") (class "Default")
      (node (ref "R12") (pin "1") (pinfunction "TOP_1") (pintype "passive"))
    )
    (net (code "46") (name "unconnected-(R22-TOP-Pad1)") (class "Default")
      (node (ref "R22") (pin "1") (pinfunction "TOP_1") (pintype "passive"))
    )
    (net (code "47") (name "unconnected-(R32-TOP-Pad1)") (class "Default")
      (node (ref "R32") (pin "1") (pinfunction "TOP_1") (pintype "passive"))
    )
  )
)
